# open-lab-VUSB-C.net
KiCad netlist of a schematic drawn in EAGLE
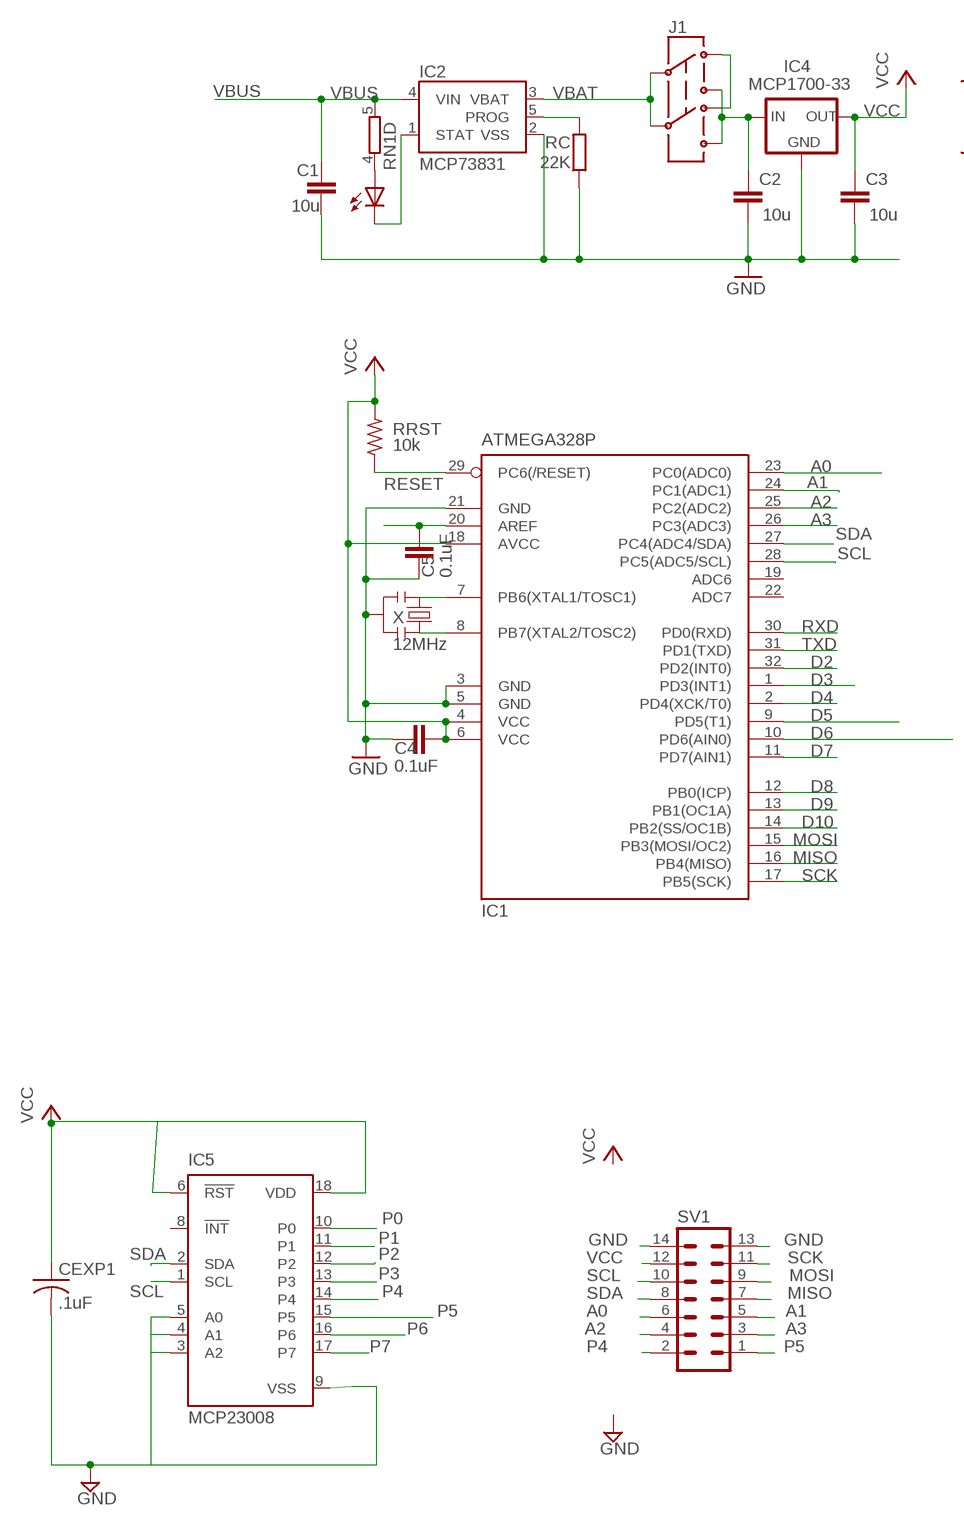
[diagram p0: schematic, sheet 1, part 1 of 2]
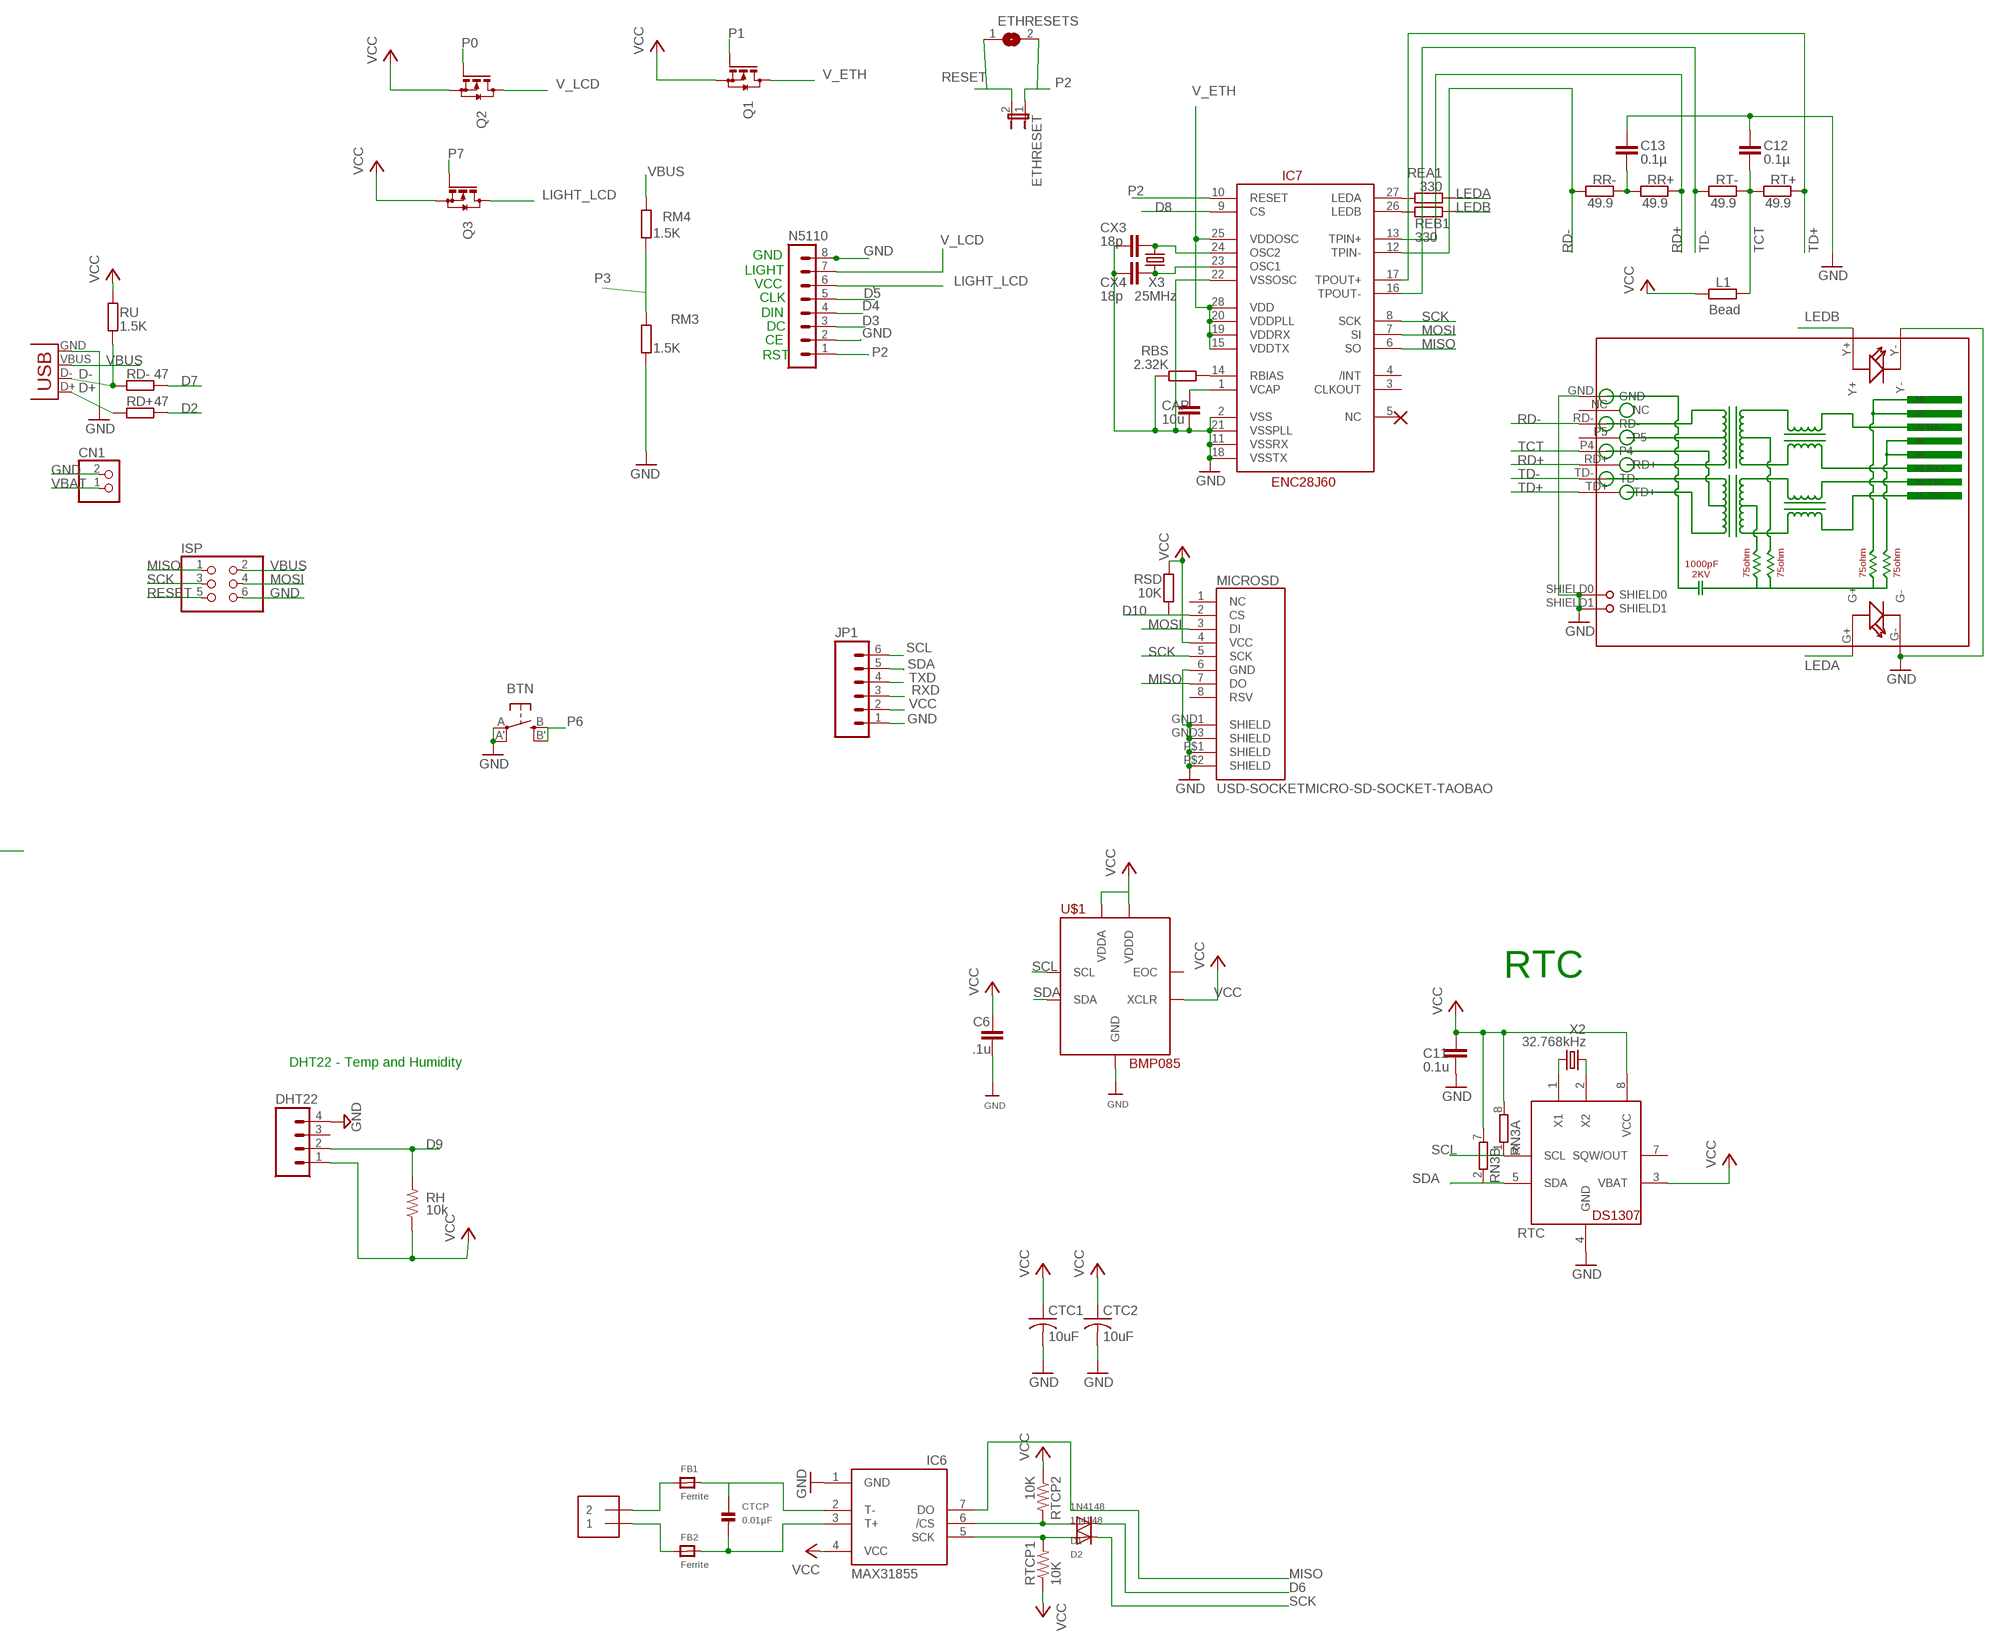
[diagram p1: schematic, sheet 1, part 2 of 2]

(export (version "E")
  (design (tool "Eeschema 10.0.6"))
  (components
    (comp (ref "BTN")
      (value "EVQQ2")
      (footprint "eagle-import:EVQ-Q2")
      (libsource (lib "eagle-import") (part "EVQQ2"))
    )
    (comp (ref "C1")
      (value "10u")
      (footprint "eagle-import:C0805")
      (libsource (lib "eagle-import") (part "resistor_C-EUC0805"))
    )
    (comp (ref "C2")
      (value "10u")
      (footprint "eagle-import:C0805")
      (libsource (lib "eagle-import") (part "resistor_C-EUC0805"))
    )
    (comp (ref "C3")
      (value "10u")
      (footprint "eagle-import:C0805")
      (libsource (lib "eagle-import") (part "resistor_C-EUC0805"))
    )
    (comp (ref "C4")
      (value "0.1uF")
      (footprint "eagle-import:C0805")
      (libsource (lib "eagle-import") (part "C-EUC0805"))
    )
    (comp (ref "C5")
      (value "0.1uF")
      (footprint "eagle-import:C0805")
      (libsource (lib "eagle-import") (part "C-EUC0805"))
    )
    (comp (ref "C6")
      (value ".1u")
      (footprint "eagle-import:C0805")
      (libsource (lib "eagle-import") (part "resistor_C-EUC0805"))
    )
    (comp (ref "C11")
      (value "0.1u")
      (footprint "eagle-import:C0805")
      (libsource (lib "eagle-import") (part "C-EUC0805"))
    )
    (comp (ref "C12")
      (value "0.1µ")
      (footprint "eagle-import:C0805")
      (libsource (lib "eagle-import") (part "resistor_C-EUC0805"))
    )
    (comp (ref "C13")
      (value "0.1µ")
      (footprint "eagle-import:C0805")
      (libsource (lib "eagle-import") (part "resistor_C-EUC0805"))
    )
    (comp (ref "CAP")
      (value "10u")
      (footprint "eagle-import:C0805")
      (libsource (lib "eagle-import") (part "resistor_C-EUC0805"))
    )
    (comp (ref "CEXP1")
      (value ".1uF")
      (footprint "eagle-import:C0805K")
      (libsource (lib "eagle-import") (part "C-USC0805K"))
    )
    (comp (ref "CHG")
      (value "0805")
      (footprint "eagle-import:CHIPLED_0805")
      (libsource (lib "eagle-import") (part "LEDCHIPLED_0805"))
    )
    (comp (ref "CN1")
      (value "JST_2PIN-SMT-RA")
      (footprint "eagle-import:JST-PH-2-SMT-RA")
      (libsource (lib "eagle-import") (part "JST_2PIN-SMT-RA"))
    )
    (comp (ref "CTC1")
      (value "10uF")
      (footprint "eagle-import:C0805K")
      (libsource (lib "eagle-import") (part "C-USC0805K"))
    )
    (comp (ref "CTC2")
      (value "10uF")
      (footprint "eagle-import:C0805K")
      (libsource (lib "eagle-import") (part "C-USC0805K"))
    )
    (comp (ref "CTCP")
      (value "0.01µF")
      (footprint "eagle-import:_0805")
      (libsource (lib "eagle-import") (part "CAP_CERAMIC_0805"))
    )
    (comp (ref "CX3")
      (value "18p")
      (footprint "eagle-import:C0805")
      (libsource (lib "eagle-import") (part "resistor_C-EUC0805"))
    )
    (comp (ref "CX4")
      (value "18p")
      (footprint "eagle-import:C0805")
      (libsource (lib "eagle-import") (part "resistor_C-EUC0805"))
    )
    (comp (ref "D1")
      (value "1N4148")
      (footprint "eagle-import:SOD-323F")
      (libsource (lib "eagle-import") (part "DIODESOD-323F"))
    )
    (comp (ref "D2")
      (value "1n4148")
      (footprint "eagle-import:SOD-323F")
      (libsource (lib "eagle-import") (part "DIODESOD-323F"))
    )
    (comp (ref "DHT22")
      (value "M04LOCK")
      (footprint "eagle-import:1X04_LOCK")
      (libsource (lib "eagle-import") (part "M04LOCK"))
    )
    (comp (ref "ETHRESET")
      (value "JP1E")
      (footprint "eagle-import:JP1")
      (libsource (lib "eagle-import") (part "JP1E"))
    )
    (comp (ref "ETHRESETS")
      (value "SJ")
      (footprint "eagle-import:SJ")
      (libsource (lib "eagle-import") (part "SJ"))
    )
    (comp (ref "FB1")
      (value "Ferrite")
      (footprint "eagle-import:_0805")
      (libsource (lib "eagle-import") (part "FERRITE_0805"))
    )
    (comp (ref "FB2")
      (value "Ferrite")
      (footprint "eagle-import:_0805")
      (libsource (lib "eagle-import") (part "FERRITE_0805"))
    )
    (comp (ref "IC1")
      (value "ATMEGA328P")
      (footprint "eagle-import:TQFP32-08")
      (fields (field (name "MPN") "ATMEGA8-16AU"))
      (libsource (lib "eagle-import") (part "MEGA8-AI"))
    )
    (comp (ref "IC2")
      (value "MCP73831")
      (footprint "eagle-import:SOT23-5")
      (libsource (lib "eagle-import") (part "MCP73831"))
    )
    (comp (ref "IC4")
      (value "MCP1700-33")
      (footprint "eagle-import:SOT23")
      (libsource (lib "eagle-import") (part "MCP1700SOT233"))
    )
    (comp (ref "IC5")
      (value "MCP23008")
      (footprint "eagle-import:SO18W")
      (libsource (lib "eagle-import") (part "MCP23008T"))
    )
    (comp (ref "IC6")
      (value "MAX31855")
      (footprint "eagle-import:SO08")
      (libsource (lib "eagle-import") (part "MAX6675"))
    )
    (comp (ref "IC7")
      (value "ENC28J60")
      (footprint "eagle-import:SOIC28WLONG")
      (libsource (lib "eagle-import") (part "ENC28J60SO28LONG"))
    )
    (comp (ref "ISP")
      (value "PINHD-2X3")
      (footprint "eagle-import:2X03")
      (libsource (lib "eagle-import") (part "PINHD-2X3"))
    )
    (comp (ref "J1")
      (value "AYZ0202")
      (footprint "eagle-import:AYZ0202")
      (libsource (lib "eagle-import") (part "AYZ0202"))
    )
    (comp (ref "JP1")
      (value "M06LOCK")
      (footprint "eagle-import:1X06_LOCK")
      (libsource (lib "eagle-import") (part "M06LOCK"))
    )
    (comp (ref "L1")
      (value "Bead")
      (footprint "eagle-import:R0805")
      (libsource (lib "eagle-import") (part "R-EU_R0805"))
    )
    (comp (ref "MICROSD")
      (value "USD-SOCKETMICRO-SD-SOCKET-TAOBAO")
      (footprint "eagle-import:MICRO-SD-SOCKET-TAOBAO")
      (libsource (lib "eagle-import") (part "USD-SOCKETMICRO-SD-SOCKET-TAOBAO"))
    )
    (comp (ref "N5110")
      (value "MA08-1")
      (footprint "eagle-import:MA08-1")
      (libsource (lib "eagle-import") (part "MA08-1"))
    )
    (comp (ref "Q1")
      (value "BSS123")
      (footprint "eagle-import:SOT23")
      (libsource (lib "eagle-import") (part "BSS123"))
    )
    (comp (ref "Q2")
      (value "BSS123")
      (footprint "eagle-import:SOT23")
      (libsource (lib "eagle-import") (part "BSS123"))
    )
    (comp (ref "Q3")
      (value "BSS123")
      (footprint "eagle-import:SOT23")
      (libsource (lib "eagle-import") (part "BSS123"))
    )
    (comp (ref "RBS")
      (value "2.32K")
      (footprint "eagle-import:R0805")
      (libsource (lib "eagle-import") (part "R-EU_R0805"))
    )
    (comp (ref "RC")
      (value "22K")
      (footprint "eagle-import:R0805")
      (libsource (lib "eagle-import") (part "R-EU_R0805"))
    )
    (comp (ref "RD+")
      (value "47")
      (footprint "eagle-import:R0805")
      (libsource (lib "eagle-import") (part "R-EU_R0805"))
    )
    (comp (ref "RD-")
      (value "47")
      (footprint "eagle-import:R0805")
      (libsource (lib "eagle-import") (part "R-EU_R0805"))
    )
    (comp (ref "REA1")
      (value "330")
      (footprint "eagle-import:R0805")
      (libsource (lib "eagle-import") (part "R-EU_R0805"))
    )
    (comp (ref "REB1")
      (value "330")
      (footprint "eagle-import:R0805")
      (libsource (lib "eagle-import") (part "R-EU_R0805"))
    )
    (comp (ref "RH")
      (value "10k")
      (footprint "eagle-import:R0805@1")
      (libsource (lib "eagle-import") (part "rcl_R-US_R0805"))
    )
    (comp (ref "RJ45")
      (value "HR911105A")
      (footprint "eagle-import:HR911105A")
      (libsource (lib "eagle-import") (part "HR911105A"))
    )
    (comp (ref "RM3")
      (value "1.5K")
      (footprint "eagle-import:R0805")
      (libsource (lib "eagle-import") (part "R-EU_R0805"))
    )
    (comp (ref "RM4")
      (value "1.5K")
      (footprint "eagle-import:R0805")
      (libsource (lib "eagle-import") (part "R-EU_R0805"))
    )
    (comp (ref "RN1")
      (value "4R-NEXB38V")
      (footprint "eagle-import:EXB38V")
      (libsource (lib "eagle-import") (part "4R-NEXB38V"))
    )
    (comp (ref "RN3")
      (value "4R-NEXB38V")
      (footprint "eagle-import:EXB38V")
      (libsource (lib "eagle-import") (part "4R-NEXB38V"))
    )
    (comp (ref "RR+")
      (value "49.9")
      (footprint "eagle-import:R0805")
      (libsource (lib "eagle-import") (part "R-EU_R0805"))
    )
    (comp (ref "RR-")
      (value "49.9")
      (footprint "eagle-import:R0805")
      (libsource (lib "eagle-import") (part "R-EU_R0805"))
    )
    (comp (ref "RRST")
      (value "10k")
      (footprint "eagle-import:R0805@1")
      (libsource (lib "eagle-import") (part "rcl_R-US_R0805"))
    )
    (comp (ref "RSD")
      (value "10K")
      (footprint "eagle-import:R0805")
      (libsource (lib "eagle-import") (part "R-EU_R0805"))
    )
    (comp (ref "RT+")
      (value "49.9")
      (footprint "eagle-import:R0805")
      (libsource (lib "eagle-import") (part "R-EU_R0805"))
    )
    (comp (ref "RT-")
      (value "49.9")
      (footprint "eagle-import:R0805")
      (libsource (lib "eagle-import") (part "R-EU_R0805"))
    )
    (comp (ref "RTC")
      (value "DS1307")
      (footprint "eagle-import:SO08")
      (libsource (lib "eagle-import") (part "DS1307SOIC"))
    )
    (comp (ref "RTCP1")
      (value "10K")
      (footprint "eagle-import:R0805")
      (libsource (lib "eagle-import") (part "R-US_R0805"))
    )
    (comp (ref "RTCP2")
      (value "10K")
      (footprint "eagle-import:R0805")
      (libsource (lib "eagle-import") (part "R-US_R0805"))
    )
    (comp (ref "RU")
      (value "1.5K")
      (footprint "eagle-import:R0805")
      (libsource (lib "eagle-import") (part "R-EU_R0805"))
    )
    (comp (ref "SV1")
      (value "MA07-2")
      (footprint "eagle-import:MA07-2")
      (libsource (lib "eagle-import") (part "MA07-2"))
    )
    (comp (ref "TCPL")
      (value "1X2-3.5MM")
      (footprint "eagle-import:1X2-3.5MM")
      (libsource (lib "eagle-import") (part "1X2-3.5MM"))
    )
    (comp (ref "U$1")
      (value "BMP085")
      (footprint "eagle-import:BMP085")
      (libsource (lib "eagle-import") (part "BMP085"))
    )
    (comp (ref "X")
      (value "12MHz")
      (footprint "eagle-import:RESONATOR-SMD")
      (libsource (lib "eagle-import") (part "RESONATORSMD"))
    )
    (comp (ref "X1")
      (value "USBSMD")
      (footprint "eagle-import:USB-MINIB")
      (libsource (lib "eagle-import") (part "USBSMD"))
    )
    (comp (ref "X2")
      (value "32.768kHz")
      (footprint "eagle-import:TC26H")
      (libsource (lib "eagle-import") (part "crystal_CRYSTALTC26H"))
    )
    (comp (ref "X3")
      (value "25MHz")
      (footprint "eagle-import:HC49U-V")
      (libsource (lib "eagle-import") (part "CRYSTALHC49UV"))
    )
  )
  (nets
    (net (code "1") (name "/A0") (class "Default")
      (node (ref "IC1") (pin "23") (pinfunction "PC0(ADC0)_23") (pintype "bidirectional"))
      (node (ref "SV1") (pin "6") (pinfunction "6_6") (pintype "passive"))
    )
    (net (code "2") (name "/A1") (class "Default")
      (node (ref "IC1") (pin "24") (pinfunction "PC1(ADC1)_24") (pintype "bidirectional"))
      (node (ref "SV1") (pin "5") (pinfunction "5_5") (pintype "passive"))
    )
    (net (code "3") (name "/A2") (class "Default")
      (node (ref "IC1") (pin "25") (pinfunction "PC2(ADC2)_25") (pintype "bidirectional"))
      (node (ref "SV1") (pin "4") (pinfunction "4_4") (pintype "passive"))
    )
    (net (code "4") (name "/A3") (class "Default")
      (node (ref "IC1") (pin "26") (pinfunction "PC3(ADC3)_26") (pintype "bidirectional"))
      (node (ref "SV1") (pin "3") (pinfunction "3_3") (pintype "passive"))
    )
    (net (code "5") (name "/D+") (class "Default")
      (node (ref "RD+") (pin "1") (pinfunction "1_1") (pintype "passive"))
      (node (ref "X1") (pin "D+") (pinfunction "D+_D+") (pintype "bidirectional"))
    )
    (net (code "6") (name "/D-") (class "Default")
      (node (ref "RD-") (pin "1") (pinfunction "1_1") (pintype "passive"))
      (node (ref "RU") (pin "1") (pinfunction "1_1") (pintype "passive"))
      (node (ref "X1") (pin "D-") (pinfunction "D-_D-") (pintype "bidirectional"))
    )
    (net (code "7") (name "/D2") (class "Default")
      (node (ref "IC1") (pin "32") (pinfunction "PD2(INT0)_32") (pintype "bidirectional"))
      (node (ref "RD+") (pin "2") (pinfunction "2_2") (pintype "passive"))
    )
    (net (code "8") (name "/D3") (class "Default")
      (node (ref "IC1") (pin "1") (pinfunction "PD3(INT1)_1") (pintype "bidirectional"))
      (node (ref "N5110") (pin "3") (pinfunction "3_3") (pintype "passive"))
    )
    (net (code "9") (name "/D4") (class "Default")
      (node (ref "IC1") (pin "2") (pinfunction "PD4(XCK/T0)_2") (pintype "bidirectional"))
      (node (ref "N5110") (pin "4") (pinfunction "4_4") (pintype "passive"))
    )
    (net (code "10") (name "/D5") (class "Default")
      (node (ref "IC1") (pin "9") (pinfunction "PD5(T1)_9") (pintype "bidirectional"))
      (node (ref "N5110") (pin "5") (pinfunction "5_5") (pintype "passive"))
    )
    (net (code "11") (name "/D6") (class "Default")
      (node (ref "D1") (pin "C") (pinfunction "C_C") (pintype "passive"))
      (node (ref "IC1") (pin "10") (pinfunction "PD6(AIN0)_10") (pintype "bidirectional"))
    )
    (net (code "12") (name "/D7") (class "Default")
      (node (ref "IC1") (pin "11") (pinfunction "PD7(AIN1)_11") (pintype "bidirectional"))
      (node (ref "RD-") (pin "2") (pinfunction "2_2") (pintype "passive"))
    )
    (net (code "13") (name "/D8") (class "Default")
      (node (ref "IC1") (pin "12") (pinfunction "PB0(ICP)_12") (pintype "bidirectional"))
      (node (ref "IC7") (pin "9") (pinfunction "CS_9") (pintype "bidirectional"))
    )
    (net (code "14") (name "/D9") (class "Default")
      (node (ref "DHT22") (pin "2") (pinfunction "2_2") (pintype "passive"))
      (node (ref "IC1") (pin "13") (pinfunction "PB1(OC1A)_13") (pintype "bidirectional"))
      (node (ref "RH") (pin "2") (pinfunction "2_2") (pintype "passive"))
    )
    (net (code "15") (name "/D10") (class "Default")
      (node (ref "IC1") (pin "14") (pinfunction "PB2(SS/OC1B)_14") (pintype "bidirectional"))
      (node (ref "MICROSD") (pin "2") (pinfunction "CS_2") (pintype "bidirectional"))
      (node (ref "RSD") (pin "1") (pinfunction "1_1") (pintype "passive"))
    )
    (net (code "16") (name "/LEDA") (class "Default")
      (node (ref "REA1") (pin "2") (pinfunction "2_2") (pintype "passive"))
      (node (ref "RJ45") (pin "G+") (pinfunction "G+_G+") (pintype "bidirectional"))
    )
    (net (code "17") (name "/LEDB") (class "Default")
      (node (ref "REB1") (pin "2") (pinfunction "2_2") (pintype "passive"))
      (node (ref "RJ45") (pin "Y+") (pinfunction "Y+_Y+") (pintype "bidirectional"))
    )
    (net (code "18") (name "/LIGHT_LCD") (class "Default")
      (node (ref "N5110") (pin "6") (pinfunction "6_6") (pintype "passive"))
      (node (ref "Q3") (pin "3") (pinfunction "D_3") (pintype "passive"))
    )
    (net (code "19") (name "/MISO") (class "Default")
      (node (ref "IC1") (pin "16") (pinfunction "PB4(MISO)_16") (pintype "bidirectional"))
      (node (ref "IC6") (pin "7") (pinfunction "DO_7") (pintype "output"))
      (node (ref "IC7") (pin "6") (pinfunction "SO_6") (pintype "bidirectional"))
      (node (ref "ISP") (pin "1") (pinfunction "1_1") (pintype "passive"))
      (node (ref "MICROSD") (pin "7") (pinfunction "DO_7") (pintype "bidirectional"))
      (node (ref "SV1") (pin "7") (pinfunction "7_7") (pintype "passive"))
    )
    (net (code "20") (name "/MOSI") (class "Default")
      (node (ref "IC1") (pin "15") (pinfunction "PB3(MOSI/OC2)_15") (pintype "bidirectional"))
      (node (ref "IC7") (pin "7") (pinfunction "SI_7") (pintype "bidirectional"))
      (node (ref "ISP") (pin "4") (pinfunction "4_4") (pintype "passive"))
      (node (ref "MICROSD") (pin "3") (pinfunction "DI_3") (pintype "bidirectional"))
      (node (ref "SV1") (pin "9") (pinfunction "9_9") (pintype "passive"))
    )
    (net (code "21") (name "/P0") (class "Default")
      (node (ref "IC5") (pin "10") (pinfunction "P0_10") (pintype "bidirectional"))
      (node (ref "Q2") (pin "1") (pinfunction "G_1") (pintype "passive"))
    )
    (net (code "22") (name "/P1") (class "Default")
      (node (ref "IC5") (pin "11") (pinfunction "P1_11") (pintype "bidirectional"))
      (node (ref "Q1") (pin "1") (pinfunction "G_1") (pintype "passive"))
    )
    (net (code "23") (name "/P2") (class "Default")
      (node (ref "ETHRESET") (pin "1") (pinfunction "1_1") (pintype "passive"))
      (node (ref "ETHRESETS") (pin "2") (pinfunction "2_2") (pintype "passive"))
      (node (ref "IC5") (pin "12") (pinfunction "P2_12") (pintype "bidirectional"))
      (node (ref "IC7") (pin "10") (pinfunction "RESET_10") (pintype "bidirectional"))
      (node (ref "N5110") (pin "1") (pinfunction "1_1") (pintype "passive"))
    )
    (net (code "24") (name "/P3") (class "Default")
      (node (ref "IC5") (pin "13") (pinfunction "P3_13") (pintype "bidirectional"))
      (node (ref "RM3") (pin "2") (pinfunction "2_2") (pintype "passive"))
      (node (ref "RM4") (pin "1") (pinfunction "1_1") (pintype "passive"))
    )
    (net (code "25") (name "/P4") (class "Default")
      (node (ref "IC5") (pin "14") (pinfunction "P4_14") (pintype "bidirectional"))
      (node (ref "SV1") (pin "2") (pinfunction "2_2") (pintype "passive"))
    )
    (net (code "26") (name "/P5") (class "Default")
      (node (ref "IC5") (pin "15") (pinfunction "P5_15") (pintype "bidirectional"))
      (node (ref "SV1") (pin "1") (pinfunction "1_1") (pintype "passive"))
    )
    (net (code "27") (name "/P6") (class "Default")
      (node (ref "BTN") (pin "B") (pinfunction "S_B") (pintype "passive"))
      (node (ref "BTN") (pin "B'") (pinfunction "S1_B'") (pintype "passive"))
      (node (ref "IC5") (pin "16") (pinfunction "P6_16") (pintype "bidirectional"))
    )
    (net (code "28") (name "/P7") (class "Default")
      (node (ref "IC5") (pin "17") (pinfunction "P7_17") (pintype "bidirectional"))
      (node (ref "Q3") (pin "1") (pinfunction "G_1") (pintype "passive"))
    )
    (net (code "29") (name "/RD+") (class "Default")
      (node (ref "IC7") (pin "13") (pinfunction "TPIN+_13") (pintype "bidirectional"))
      (node (ref "RJ45") (pin "RD+") (pinfunction "RD+_RD+") (pintype "bidirectional"))
      (node (ref "RR+") (pin "1") (pinfunction "1_1") (pintype "passive"))
    )
    (net (code "30") (name "/RD-") (class "Default")
      (node (ref "IC7") (pin "12") (pinfunction "TPIN-_12") (pintype "bidirectional"))
      (node (ref "RJ45") (pin "RD-") (pinfunction "RD-_RD-") (pintype "bidirectional"))
      (node (ref "RR-") (pin "2") (pinfunction "2_2") (pintype "passive"))
    )
    (net (code "31") (name "/RESET") (class "Default")
      (node (ref "ETHRESET") (pin "2") (pinfunction "2_2") (pintype "passive"))
      (node (ref "ETHRESETS") (pin "1") (pinfunction "1_1") (pintype "passive"))
      (node (ref "IC1") (pin "29") (pinfunction "PC6(/RESET)_29") (pintype "bidirectional"))
      (node (ref "ISP") (pin "5") (pinfunction "5_5") (pintype "passive"))
      (node (ref "RRST") (pin "1") (pinfunction "1_1") (pintype "passive"))
    )
    (net (code "32") (name "/RXD") (class "Default")
      (node (ref "IC1") (pin "30") (pinfunction "PD0(RXD)_30") (pintype "bidirectional"))
      (node (ref "JP1") (pin "3") (pinfunction "3_3") (pintype "passive"))
    )
    (net (code "33") (name "/SCK") (class "Default")
      (node (ref "D2") (pin "C") (pinfunction "C_C") (pintype "passive"))
      (node (ref "IC1") (pin "17") (pinfunction "PB5(SCK)_17") (pintype "bidirectional"))
      (node (ref "IC7") (pin "8") (pinfunction "SCK_8") (pintype "bidirectional"))
      (node (ref "ISP") (pin "3") (pinfunction "3_3") (pintype "passive"))
      (node (ref "MICROSD") (pin "5") (pinfunction "SCK_5") (pintype "bidirectional"))
      (node (ref "SV1") (pin "11") (pinfunction "11_11") (pintype "passive"))
    )
    (net (code "34") (name "/SCL") (class "Default")
      (node (ref "IC1") (pin "28") (pinfunction "PC5(ADC5/SCL)_28") (pintype "bidirectional"))
      (node (ref "IC5") (pin "1") (pinfunction "SCL_1") (pintype "input"))
      (node (ref "JP1") (pin "6") (pinfunction "6_6") (pintype "passive"))
      (node (ref "RN3") (pin "1") (pinfunction "1_1") (pintype "passive"))
      (node (ref "RTC") (pin "6") (pinfunction "SCL_6") (pintype "bidirectional"))
      (node (ref "SV1") (pin "10") (pinfunction "10_10") (pintype "passive"))
      (node (ref "U$1") (pin "P$6") (pinfunction "SCL_P$6") (pintype "bidirectional"))
    )
    (net (code "35") (name "/SDA") (class "Default")
      (node (ref "IC1") (pin "27") (pinfunction "PC4(ADC4/SDA)_27") (pintype "bidirectional"))
      (node (ref "IC5") (pin "2") (pinfunction "SDA_2") (pintype "bidirectional"))
      (node (ref "JP1") (pin "5") (pinfunction "5_5") (pintype "passive"))
      (node (ref "RN3") (pin "2") (pinfunction "1_2") (pintype "passive"))
      (node (ref "RTC") (pin "5") (pinfunction "SDA_5") (pintype "bidirectional"))
      (node (ref "SV1") (pin "8") (pinfunction "8_8") (pintype "passive"))
      (node (ref "U$1") (pin "P$7") (pinfunction "SDA_P$7") (pintype "bidirectional"))
    )
    (net (code "36") (name "/TCT") (class "Default")
      (node (ref "C12") (pin "2") (pinfunction "2_2") (pintype "passive"))
      (node (ref "L1") (pin "1") (pinfunction "1_1") (pintype "passive"))
      (node (ref "RJ45") (pin "P4") (pinfunction "P4_P4") (pintype "bidirectional"))
      (node (ref "RT+") (pin "2") (pinfunction "2_2") (pintype "passive"))
      (node (ref "RT-") (pin "1") (pinfunction "1_1") (pintype "passive"))
    )
    (net (code "37") (name "/TD+") (class "Default")
      (node (ref "IC7") (pin "17") (pinfunction "TPOUT+_17") (pintype "bidirectional"))
      (node (ref "RJ45") (pin "TD+") (pinfunction "TD+_TD+") (pintype "bidirectional"))
      (node (ref "RT+") (pin "1") (pinfunction "1_1") (pintype "passive"))
    )
    (net (code "38") (name "/TD-") (class "Default")
      (node (ref "IC7") (pin "16") (pinfunction "TPOUT-_16") (pintype "bidirectional"))
      (node (ref "RJ45") (pin "TD-") (pinfunction "TD-_TD-") (pintype "bidirectional"))
      (node (ref "RT-") (pin "2") (pinfunction "2_2") (pintype "passive"))
    )
    (net (code "39") (name "/TXD") (class "Default")
      (node (ref "IC1") (pin "31") (pinfunction "PD1(TXD)_31") (pintype "bidirectional"))
      (node (ref "JP1") (pin "4") (pinfunction "4_4") (pintype "passive"))
    )
    (net (code "40") (name "/VBAT") (class "Default")
      (node (ref "CN1") (pin "1") (pinfunction "2_1") (pintype "passive"))
      (node (ref "IC2") (pin "3") (pinfunction "VBAT_3") (pintype "power_in"))
      (node (ref "J1") (pin "2") (pinfunction "2_2") (pintype "bidirectional"))
      (node (ref "J1") (pin "5") (pinfunction "5_5") (pintype "bidirectional"))
    )
    (net (code "41") (name "/VBUS") (class "Default")
      (node (ref "C1") (pin "1") (pinfunction "1_1") (pintype "passive"))
      (node (ref "IC2") (pin "4") (pinfunction "VIN_4") (pintype "power_in"))
      (node (ref "ISP") (pin "2") (pinfunction "2_2") (pintype "passive"))
      (node (ref "RM4") (pin "2") (pinfunction "2_2") (pintype "passive"))
      (node (ref "RN1") (pin "5") (pinfunction "2_5") (pintype "passive"))
      (node (ref "X1") (pin "VBUS") (pinfunction "VBUS_VBUS") (pintype "bidirectional"))
    )
    (net (code "42") (name "/V_ETH") (class "Default")
      (node (ref "IC7") (pin "15") (pinfunction "VDDTX_15") (pintype "bidirectional"))
      (node (ref "IC7") (pin "19") (pinfunction "VDDRX_19") (pintype "bidirectional"))
      (node (ref "IC7") (pin "20") (pinfunction "VDDPLL_20") (pintype "bidirectional"))
      (node (ref "IC7") (pin "25") (pinfunction "VDDOSC_25") (pintype "bidirectional"))
      (node (ref "IC7") (pin "28") (pinfunction "VDD_28") (pintype "bidirectional"))
      (node (ref "Q1") (pin "3") (pinfunction "D_3") (pintype "passive"))
    )
    (net (code "43") (name "/V_LCD") (class "Default")
      (node (ref "N5110") (pin "7") (pinfunction "7_7") (pintype "passive"))
      (node (ref "Q2") (pin "3") (pinfunction "D_3") (pintype "passive"))
    )
    (net (code "44") (name "GND") (class "Default")
      (node (ref "BTN") (pin "A") (pinfunction "P_A") (pintype "passive"))
      (node (ref "BTN") (pin "A'") (pinfunction "P1_A'") (pintype "passive"))
      (node (ref "C1") (pin "2") (pinfunction "2_2") (pintype "passive"))
      (node (ref "C11") (pin "2") (pinfunction "2_2") (pintype "passive"))
      (node (ref "C12") (pin "1") (pinfunction "1_1") (pintype "passive"))
      (node (ref "C13") (pin "1") (pinfunction "1_1") (pintype "passive"))
      (node (ref "C2") (pin "2") (pinfunction "2_2") (pintype "passive"))
      (node (ref "C3") (pin "2") (pinfunction "2_2") (pintype "passive"))
      (node (ref "C4") (pin "1") (pinfunction "1_1") (pintype "passive"))
      (node (ref "C5") (pin "1") (pinfunction "1_1") (pintype "passive"))
      (node (ref "C6") (pin "2") (pinfunction "2_2") (pintype "passive"))
      (node (ref "CAP") (pin "2") (pinfunction "2_2") (pintype "passive"))
      (node (ref "CEXP1") (pin "2") (pinfunction "2_2") (pintype "passive"))
      (node (ref "CN1") (pin "2") (pinfunction "1_2") (pintype "passive"))
      (node (ref "CTC1") (pin "2") (pinfunction "2_2") (pintype "passive"))
      (node (ref "CTC2") (pin "2") (pinfunction "2_2") (pintype "passive"))
      (node (ref "CX3") (pin "2") (pinfunction "2_2") (pintype "passive"))
      (node (ref "CX4") (pin "2") (pinfunction "2_2") (pintype "passive"))
      (node (ref "DHT22") (pin "4") (pinfunction "4_4") (pintype "passive"))
      (node (ref "IC1") (pin "21") (pinfunction "GND_21") (pintype "power_in"))
      (node (ref "IC1") (pin "3") (pinfunction "GND_3") (pintype "power_in"))
      (node (ref "IC1") (pin "5") (pinfunction "GND_5") (pintype "power_in"))
      (node (ref "IC2") (pin "2") (pinfunction "VSS_2") (pintype "power_in"))
      (node (ref "IC4") (pin "1") (pinfunction "GND_1") (pintype "input"))
      (node (ref "IC5") (pin "3") (pinfunction "A2_3") (pintype "input"))
      (node (ref "IC5") (pin "4") (pinfunction "A1_4") (pintype "input"))
      (node (ref "IC5") (pin "5") (pinfunction "A0_5") (pintype "input"))
      (node (ref "IC5") (pin "9") (pinfunction "VSS_9") (pintype "power_in"))
      (node (ref "IC6") (pin "1") (pinfunction "GND_1") (pintype "power_in"))
      (node (ref "IC7") (pin "11") (pinfunction "VSSRX_11") (pintype "bidirectional"))
      (node (ref "IC7") (pin "18") (pinfunction "VSSTX_18") (pintype "bidirectional"))
      (node (ref "IC7") (pin "2") (pinfunction "VSS_2") (pintype "bidirectional"))
      (node (ref "IC7") (pin "21") (pinfunction "VSSPLL_21") (pintype "bidirectional"))
      (node (ref "IC7") (pin "22") (pinfunction "VSSOSC_22") (pintype "bidirectional"))
      (node (ref "ISP") (pin "6") (pinfunction "6_6") (pintype "passive"))
      (node (ref "JP1") (pin "1") (pinfunction "1_1") (pintype "passive"))
      (node (ref "MICROSD") (pin "6") (pinfunction "GND_6") (pintype "bidirectional"))
      (node (ref "MICROSD") (pin "GND1") (pinfunction "SHIELD_GND1") (pintype "bidirectional"))
      (node (ref "MICROSD") (pin "GND3") (pinfunction "SHIELD_GND3") (pintype "bidirectional"))
      (node (ref "MICROSD") (pin "P$1") (pinfunction "SHIELD_P$1") (pintype "bidirectional"))
      (node (ref "MICROSD") (pin "P$2") (pinfunction "SHIELD_P$2") (pintype "bidirectional"))
      (node (ref "N5110") (pin "2") (pinfunction "2_2") (pintype "passive"))
      (node (ref "N5110") (pin "8") (pinfunction "8_8") (pintype "passive"))
      (node (ref "RBS") (pin "1") (pinfunction "1_1") (pintype "passive"))
      (node (ref "RC") (pin "1") (pinfunction "1_1") (pintype "passive"))
      (node (ref "RJ45") (pin "G-") (pinfunction "G-_G-") (pintype "bidirectional"))
      (node (ref "RJ45") (pin "GND") (pinfunction "GND_GND") (pintype "bidirectional"))
      (node (ref "RJ45") (pin "SHIELD0") (pinfunction "SHIELD0_SHIELD0") (pintype "bidirectional"))
      (node (ref "RJ45") (pin "SHIELD1") (pinfunction "SHIELD1_SHIELD1") (pintype "bidirectional"))
      (node (ref "RJ45") (pin "Y-") (pinfunction "Y-_Y-") (pintype "bidirectional"))
      (node (ref "RM3") (pin "1") (pinfunction "1_1") (pintype "passive"))
      (node (ref "RTC") (pin "4") (pinfunction "GND_4") (pintype "power_in"))
      (node (ref "SV1") (pin "13") (pinfunction "13_13") (pintype "passive"))
      (node (ref "SV1") (pin "14") (pinfunction "14_14") (pintype "passive"))
      (node (ref "U$1") (pin "P$1") (pinfunction "GND_P$1") (pintype "power_in"))
      (node (ref "X") (pin "2") (pinfunction "2_2") (pintype "passive"))
      (node (ref "X1") (pin "GND") (pinfunction "GND_GND") (pintype "bidirectional"))
    )
    (net (code "45") (name "Net-(C13-Pad2)") (class "Default")
      (node (ref "C13") (pin "2") (pinfunction "2_2") (pintype "passive"))
      (node (ref "RR+") (pin "2") (pinfunction "2_2") (pintype "passive"))
      (node (ref "RR-") (pin "1") (pinfunction "1_1") (pintype "passive"))
    )
    (net (code "46") (name "Net-(CTCP-P$1)") (class "Default")
      (node (ref "CTCP") (pin "1") (pinfunction "P$1_1") (pintype "passive"))
      (node (ref "FB1") (pin "2") (pinfunction "P$2_2") (pintype "passive"))
      (node (ref "IC6") (pin "2") (pinfunction "T-_2") (pintype "input"))
    )
    (net (code "47") (name "Net-(CTCP-P$2)") (class "Default")
      (node (ref "CTCP") (pin "2") (pinfunction "P$2_2") (pintype "passive"))
      (node (ref "FB2") (pin "2") (pinfunction "P$2_2") (pintype "passive"))
      (node (ref "IC6") (pin "3") (pinfunction "T+_3") (pintype "input"))
    )
    (net (code "48") (name "Net-(FB1-P$1)") (class "Default")
      (node (ref "FB1") (pin "1") (pinfunction "P$1_1") (pintype "passive"))
      (node (ref "TCPL") (pin "2") (pinfunction "2_2") (pintype "passive"))
    )
    (net (code "49") (name "Net-(FB2-P$1)") (class "Default")
      (node (ref "FB2") (pin "1") (pinfunction "P$1_1") (pintype "passive"))
      (node (ref "TCPL") (pin "1") (pinfunction "1_1") (pintype "passive"))
    )
    (net (code "50") (name "Net-(IC1-AREF)") (class "Default")
      (node (ref "C5") (pin "2") (pinfunction "2_2") (pintype "passive"))
      (node (ref "IC1") (pin "20") (pinfunction "AREF_20") (pintype "passive"))
    )
    (net (code "51") (name "Net-(IC1-PB6(XTAL1{slash}TOSC1))") (class "Default")
      (node (ref "IC1") (pin "7") (pinfunction "PB6(XTAL1/TOSC1)_7") (pintype "bidirectional"))
      (node (ref "X") (pin "1") (pinfunction "1_1") (pintype "passive"))
    )
    (net (code "52") (name "Net-(IC1-PB7(XTAL2{slash}TOSC2))") (class "Default")
      (node (ref "IC1") (pin "8") (pinfunction "PB7(XTAL2/TOSC2)_8") (pintype "bidirectional"))
      (node (ref "X") (pin "3") (pinfunction "3_3") (pintype "passive"))
    )
    (net (code "53") (name "Net-(IC2-PROG)") (class "Default")
      (node (ref "IC2") (pin "5") (pinfunction "PROG_5") (pintype "input"))
      (node (ref "RC") (pin "2") (pinfunction "2_2") (pintype "passive"))
    )
    (net (code "54") (name "Net-(IC2-STAT)") (class "Default")
      (node (ref "CHG") (pin "C") (pinfunction "C_C") (pintype "passive"))
      (node (ref "IC2") (pin "1") (pinfunction "STAT_1") (pintype "output"))
    )
    (net (code "55") (name "Net-(IC4-IN)") (class "Default")
      (node (ref "C2") (pin "1") (pinfunction "1_1") (pintype "passive"))
      (node (ref "IC4") (pin "3") (pinfunction "IN_3") (pintype "input"))
      (node (ref "J1") (pin "1") (pinfunction "3_1") (pintype "bidirectional"))
      (node (ref "J1") (pin "4") (pinfunction "6_4") (pintype "bidirectional"))
    )
    (net (code "56") (name "Net-(IC6-SCK)") (class "Default")
      (node (ref "D2") (pin "A") (pinfunction "A_A") (pintype "passive"))
      (node (ref "IC6") (pin "5") (pinfunction "SCK_5") (pintype "input"))
      (node (ref "RTCP1") (pin "2") (pinfunction "2_2") (pintype "passive"))
    )
    (net (code "57") (name "Net-(IC6-{slash}CS)") (class "Default")
      (node (ref "D1") (pin "A") (pinfunction "A_A") (pintype "passive"))
      (node (ref "IC6") (pin "6") (pinfunction "/CS_6") (pintype "input"))
      (node (ref "RTCP2") (pin "2") (pinfunction "2_2") (pintype "passive"))
    )
    (net (code "58") (name "Net-(IC7-LEDA)") (class "Default")
      (node (ref "IC7") (pin "27") (pinfunction "LEDA_27") (pintype "bidirectional"))
      (node (ref "REA1") (pin "1") (pinfunction "1_1") (pintype "passive"))
    )
    (net (code "59") (name "Net-(IC7-LEDB)") (class "Default")
      (node (ref "IC7") (pin "26") (pinfunction "LEDB_26") (pintype "bidirectional"))
      (node (ref "REB1") (pin "1") (pinfunction "1_1") (pintype "passive"))
    )
    (net (code "60") (name "Net-(IC7-OSC1)") (class "Default")
      (node (ref "CX4") (pin "1") (pinfunction "1_1") (pintype "passive"))
      (node (ref "IC7") (pin "23") (pinfunction "OSC1_23") (pintype "bidirectional"))
      (node (ref "X3") (pin "1") (pinfunction "1_1") (pintype "passive"))
    )
    (net (code "61") (name "Net-(IC7-OSC2)") (class "Default")
      (node (ref "CX3") (pin "1") (pinfunction "1_1") (pintype "passive"))
      (node (ref "IC7") (pin "24") (pinfunction "OSC2_24") (pintype "bidirectional"))
      (node (ref "X3") (pin "2") (pinfunction "2_2") (pintype "passive"))
    )
    (net (code "62") (name "Net-(IC7-RBIAS)") (class "Default")
      (node (ref "IC7") (pin "14") (pinfunction "RBIAS_14") (pintype "bidirectional"))
      (node (ref "RBS") (pin "2") (pinfunction "2_2") (pintype "passive"))
    )
    (net (code "63") (name "Net-(IC7-VCAP)") (class "Default")
      (node (ref "CAP") (pin "1") (pinfunction "1_1") (pintype "passive"))
      (node (ref "IC7") (pin "1") (pinfunction "VCAP_1") (pintype "bidirectional"))
    )
    (net (code "64") (name "Net-(J1-1)") (class "Default")
      (node (ref "J1") (pin "3") (pinfunction "1_3") (pintype "bidirectional"))
      (node (ref "J1") (pin "6") (pinfunction "4_6") (pintype "bidirectional"))
    )
    (net (code "65") (name "Net-(RN1D-1)") (class "Default")
      (node (ref "CHG") (pin "A") (pinfunction "A_A") (pintype "passive"))
      (node (ref "RN1") (pin "4") (pinfunction "1_4") (pintype "passive"))
    )
    (net (code "66") (name "Net-(RTC-X1)") (class "Default")
      (node (ref "RTC") (pin "1") (pinfunction "X1_1") (pintype "passive"))
      (node (ref "X2") (pin "2") (pinfunction "2_2") (pintype "passive"))
    )
    (net (code "67") (name "Net-(RTC-X2)") (class "Default")
      (node (ref "RTC") (pin "2") (pinfunction "X2_2") (pintype "passive"))
      (node (ref "X2") (pin "1") (pinfunction "1_1") (pintype "passive"))
    )
    (net (code "68") (name "VCC") (class "Default")
      (node (ref "C11") (pin "1") (pinfunction "1_1") (pintype "passive"))
      (node (ref "C3") (pin "1") (pinfunction "1_1") (pintype "passive"))
      (node (ref "C4") (pin "2") (pinfunction "2_2") (pintype "passive"))
      (node (ref "C6") (pin "1") (pinfunction "1_1") (pintype "passive"))
      (node (ref "CEXP1") (pin "1") (pinfunction "1_1") (pintype "passive"))
      (node (ref "CTC1") (pin "1") (pinfunction "1_1") (pintype "passive"))
      (node (ref "CTC2") (pin "1") (pinfunction "1_1") (pintype "passive"))
      (node (ref "DHT22") (pin "1") (pinfunction "1_1") (pintype "passive"))
      (node (ref "IC1") (pin "18") (pinfunction "AVCC_18") (pintype "power_in"))
      (node (ref "IC1") (pin "4") (pinfunction "VCC_4") (pintype "power_in"))
      (node (ref "IC1") (pin "6") (pinfunction "VCC_6") (pintype "power_in"))
      (node (ref "IC4") (pin "2") (pinfunction "OUT_2") (pintype "passive"))
      (node (ref "IC5") (pin "18") (pinfunction "VDD_18") (pintype "power_in"))
      (node (ref "IC5") (pin "6") (pinfunction "~{RST}_6") (pintype "input"))
      (node (ref "IC6") (pin "4") (pinfunction "VCC_4") (pintype "power_in"))
      (node (ref "JP1") (pin "2") (pinfunction "2_2") (pintype "passive"))
      (node (ref "L1") (pin "2") (pinfunction "2_2") (pintype "passive"))
      (node (ref "MICROSD") (pin "4") (pinfunction "VCC_4") (pintype "bidirectional"))
      (node (ref "Q1") (pin "2") (pinfunction "S_2") (pintype "passive"))
      (node (ref "Q2") (pin "2") (pinfunction "S_2") (pintype "passive"))
      (node (ref "Q3") (pin "2") (pinfunction "S_2") (pintype "passive"))
      (node (ref "RH") (pin "1") (pinfunction "1_1") (pintype "passive"))
      (node (ref "RN3") (pin "7") (pinfunction "2_7") (pintype "passive"))
      (node (ref "RN3") (pin "8") (pinfunction "2_8") (pintype "passive"))
      (node (ref "RRST") (pin "2") (pinfunction "2_2") (pintype "passive"))
      (node (ref "RSD") (pin "2") (pinfunction "2_2") (pintype "passive"))
      (node (ref "RTC") (pin "3") (pinfunction "VBAT_3") (pintype "power_in"))
      (node (ref "RTC") (pin "8") (pinfunction "VCC_8") (pintype "power_in"))
      (node (ref "RTCP1") (pin "1") (pinfunction "1_1") (pintype "passive"))
      (node (ref "RTCP2") (pin "1") (pinfunction "1_1") (pintype "passive"))
      (node (ref "RU") (pin "2") (pinfunction "2_2") (pintype "passive"))
      (node (ref "SV1") (pin "12") (pinfunction "12_12") (pintype "passive"))
      (node (ref "U$1") (pin "P$3") (pinfunction "VDDA_P$3") (pintype "bidirectional"))
      (node (ref "U$1") (pin "P$4") (pinfunction "VDDD_P$4") (pintype "bidirectional"))
      (node (ref "U$1") (pin "P$8") (pinfunction "XCLR_P$8") (pintype "bidirectional"))
    )
    (net (code "69") (name "unconnected-(DHT22-Pad3)") (class "Default")
      (node (ref "DHT22") (pin "3") (pinfunction "3_3") (pintype "passive"))
    )
    (net (code "70") (name "unconnected-(IC1-ADC6-Pad19)") (class "Default")
      (node (ref "IC1") (pin "19") (pinfunction "ADC6_19") (pintype "bidirectional"))
    )
    (net (code "71") (name "unconnected-(IC1-ADC7-Pad22)") (class "Default")
      (node (ref "IC1") (pin "22") (pinfunction "ADC7_22") (pintype "bidirectional"))
    )
    (net (code "72") (name "unconnected-(IC5-~{INT}-Pad8)") (class "Default")
      (node (ref "IC5") (pin "8") (pinfunction "~{INT}_8") (pintype "output"))
    )
    (net (code "73") (name "unconnected-(IC7-CLKOUT-Pad3)") (class "Default")
      (node (ref "IC7") (pin "3") (pinfunction "CLKOUT_3") (pintype "bidirectional"))
    )
    (net (code "74") (name "unconnected-(IC7-NC-Pad5)") (class "Default")
      (node (ref "IC7") (pin "5") (pinfunction "NC_5") (pintype "bidirectional"))
    )
    (net (code "75") (name "unconnected-(IC7-{slash}INT-Pad4)") (class "Default")
      (node (ref "IC7") (pin "4") (pinfunction "/INT_4") (pintype "bidirectional"))
    )
    (net (code "76") (name "unconnected-(MICROSD-NC-Pad1)") (class "Default")
      (node (ref "MICROSD") (pin "1") (pinfunction "NC_1") (pintype "bidirectional"))
    )
    (net (code "77") (name "unconnected-(MICROSD-RSV-Pad8)") (class "Default")
      (node (ref "MICROSD") (pin "8") (pinfunction "RSV_8") (pintype "bidirectional"))
    )
    (net (code "78") (name "unconnected-(RJ45-PadNC)") (class "Default")
      (node (ref "RJ45") (pin "NC") (pinfunction "NC_NC") (pintype "bidirectional"))
    )
    (net (code "79") (name "unconnected-(RJ45-PadP5)") (class "Default")
      (node (ref "RJ45") (pin "P5") (pinfunction "P5_P5") (pintype "bidirectional"))
    )
    (net (code "80") (name "unconnected-(RTC-SQW{slash}OUT-Pad7)") (class "Default")
      (node (ref "RTC") (pin "7") (pinfunction "SQW/OUT_7") (pintype "bidirectional"))
    )
    (net (code "81") (name "unconnected-(U$1-EOC-PadP$2)") (class "Default")
      (node (ref "U$1") (pin "P$2") (pinfunction "EOC_P$2") (pintype "bidirectional"))
    )
  )
)
